# LEDS-managed.net
KiCad netlist of a schematic drawn in Altium Designer
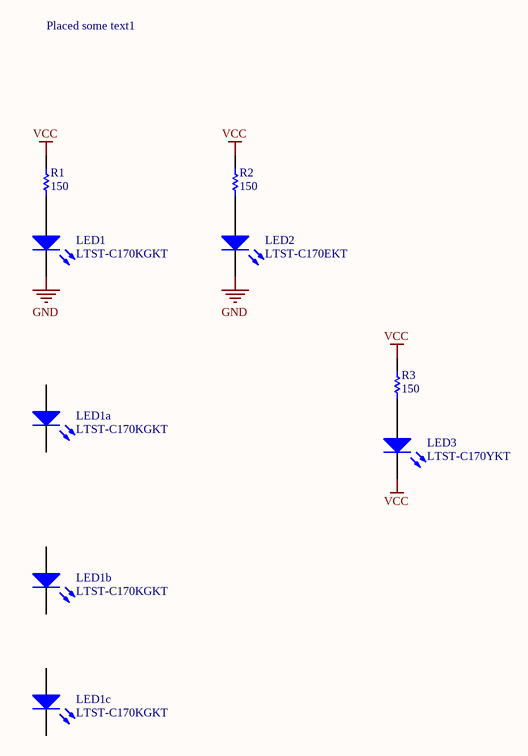
[diagram p0: LEDS-managed.SchDoc]

(export (version "E")
  (design (tool "Eeschema 10.0.6"))
  (components
    (comp (ref "LED1")
      (value "LTST-C170KGKT")
      (footprint "LED2013 - GREEN")
      (description "LED, Green 0805 (2013)")
      (libsource (lib "Flo Workspace") (part "DIO-LED-1S"))
    )
    (comp (ref "LED1a")
      (value "LTST-C170KGKT")
      (footprint "LED2013 - GREEN")
      (description "LED, Green 0805 (2013)")
      (libsource (lib "Flo Workspace") (part "DIO-LED-1S"))
    )
    (comp (ref "LED1b")
      (value "LTST-C170KGKT")
      (footprint "LED2013 - GREEN")
      (description "LED, Green 0805 (2013)")
      (libsource (lib "Flo Workspace") (part "DIO-LED-1S"))
    )
    (comp (ref "LED1c")
      (value "LTST-C170KGKT")
      (footprint "LED2013 - GREEN")
      (description "LED, Green 0805 (2013)")
      (libsource (lib "Flo Workspace") (part "DIO-LED-1S"))
    )
    (comp (ref "LED2")
      (value "LTST-C170EKT")
      (footprint "LED2013 - RED")
      (description "LED, Red 0805 (2013)")
      (libsource (lib "Flo Workspace") (part "DIO-LED-1S"))
    )
    (comp (ref "LED3")
      (value "LTST-C170YKT")
      (footprint "LED2013 - YELLOW")
      (description "LED, Yellow 0805 (2013)")
      (libsource (lib "Flo Workspace") (part "DIO-LED-1S"))
    )
    (comp (ref "R1")
      (value "150")
      (footprint "RESC60X30X26L15L (0201)")
      (description "Res, 150R, 0.05W, 1%,  0201 SMD")
      (fields (field (name "POWER") "50mW") (field (name "TOLERANCE") "0.01%"))
      (libsource (lib "Flo Workspace") (part "NUV_Res_2"))
    )
    (comp (ref "R2")
      (value "150")
      (footprint "RESC60X30X26L15L (0201)")
      (description "Res, 150R, 0.05W, 1%,  0201 SMD")
      (fields (field (name "POWER") "50mW") (field (name "TOLERANCE") "0.01%"))
      (libsource (lib "Flo Workspace") (part "NUV_Res_2"))
    )
    (comp (ref "R3")
      (value "150")
      (footprint "RESC60X30X26L15L (0201)")
      (description "Res, 150R, 0.05W, 1%,  0201 SMD")
      (fields (field (name "POWER") "50mW") (field (name "TOLERANCE") "0.01%"))
      (libsource (lib "Flo Workspace") (part "NUV_Res_2"))
    )
  )
  (nets
    (net (code "1") (name "GND") (class "Default")
      (node (ref "LED1") (pin "2") (pinfunction "K_2") (pintype "passive"))
      (node (ref "LED2") (pin "2") (pinfunction "K_2") (pintype "passive"))
    )
    (net (code "2") (name "Net-(LED1-A)") (class "Default")
      (node (ref "LED1") (pin "1") (pinfunction "A_1") (pintype "passive"))
      (node (ref "R1") (pin "1") (pinfunction "1_1") (pintype "passive"))
    )
    (net (code "3") (name "Net-(LED2-A)") (class "Default")
      (node (ref "LED2") (pin "1") (pinfunction "A_1") (pintype "passive"))
      (node (ref "R2") (pin "1") (pinfunction "1_1") (pintype "passive"))
    )
    (net (code "4") (name "Net-(LED3-A)") (class "Default")
      (node (ref "LED3") (pin "1") (pinfunction "A_1") (pintype "passive"))
      (node (ref "R3") (pin "1") (pinfunction "1_1") (pintype "passive"))
    )
    (net (code "5") (name "VCC") (class "Default")
      (node (ref "LED3") (pin "2") (pinfunction "K_2") (pintype "passive"))
      (node (ref "R1") (pin "2") (pinfunction "2_2") (pintype "passive"))
      (node (ref "R2") (pin "2") (pinfunction "2_2") (pintype "passive"))
      (node (ref "R3") (pin "2") (pinfunction "2_2") (pintype "passive"))
    )
    (net (code "6") (name "unconnected-(LED1a-A-Pad1)") (class "Default")
      (node (ref "LED1a") (pin "1") (pinfunction "A_1") (pintype "passive"))
    )
    (net (code "7") (name "unconnected-(LED1a-K-Pad2)") (class "Default")
      (node (ref "LED1a") (pin "2") (pinfunction "K_2") (pintype "passive"))
    )
    (net (code "8") (name "unconnected-(LED1b-A-Pad1)") (class "Default")
      (node (ref "LED1b") (pin "1") (pinfunction "A_1") (pintype "passive"))
    )
    (net (code "9") (name "unconnected-(LED1b-K-Pad2)") (class "Default")
      (node (ref "LED1b") (pin "2") (pinfunction "K_2") (pintype "passive"))
    )
    (net (code "10") (name "unconnected-(LED1c-A-Pad1)") (class "Default")
      (node (ref "LED1c") (pin "1") (pinfunction "A_1") (pintype "passive"))
    )
    (net (code "11") (name "unconnected-(LED1c-K-Pad2)") (class "Default")
      (node (ref "LED1c") (pin "2") (pinfunction "K_2") (pintype "passive"))
    )
  )
)
